# Power_ClockLed.net
KiCad netlist of a schematic drawn in Altium Designer
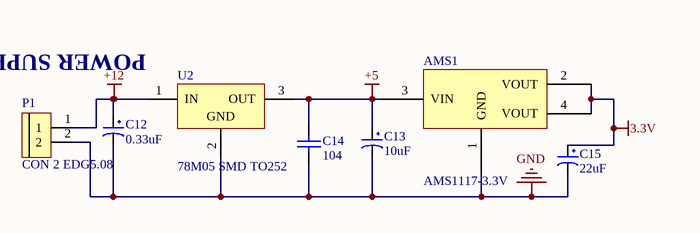
[diagram p0: Power_ClockLed.SchDoc]

(export (version "E")
  (design (tool "Eeschema 10.0.6"))
  (components
    (comp (ref "AMS1")
      (value "AMS1117-3.3V")
      (footprint "SOT223")
      (description "Dán")
      (libsource (lib "Altium_Lib_by_KhueNguyenCreator") (part "AMS1117 SMD"))
    )
    (comp (ref "C12")
      (value "0.33uF")
      (footprint "tu hoa 5mm")
      (description "Cắm")
      (libsource (lib "Altium_Lib_by_KhueNguyenCreator") (part "Tu Hoa 0.33uF 50V 5x11"))
    )
    (comp (ref "C13")
      (value "10uF")
      (footprint "tu hoa 13mm")
      (description "Cắm")
      (libsource (lib "Altium_Lib_by_KhueNguyenCreator") (part "Tu Hoa 10uF 450V 13x20"))
    )
    (comp (ref "C14")
      (value "104")
      (footprint "tu 0805")
      (description "Dán")
      (libsource (lib "Altium_Lib_by_KhueNguyenCreator") (part "Tu 0805 104 50V 10%"))
    )
    (comp (ref "C15")
      (value "22uF")
      (footprint "tu hoa 5mm")
      (description "Cắm")
      (libsource (lib "Altium_Lib_by_KhueNguyenCreator") (part "Tu Hoa 22uF 35V 5x11"))
    )
    (comp (ref "P1")
      (value "CON 2 EDG5.08")
      (footprint "CON 2 2EDG5.08")
      (description "Cắm")
      (libsource (lib "Altium_Lib_by_KhueNguyenCreator") (part "CON 2 EDG5.08"))
    )
    (comp (ref "U2")
      (value "78M05 SMD TO252")
      (footprint "TO252")
      (description "Dán")
      (libsource (lib "Altium_Lib_by_KhueNguyenCreator") (part "78M05 SMD TO252"))
    )
  )
  (nets
    (net (code "1") (name "+5") (class "Default")
      (node (ref "AMS1") (pin "3") (pinfunction "VIN_3") (pintype "passive"))
      (node (ref "C13") (pin "1") (pinfunction "1_1") (pintype "passive"))
      (node (ref "C14") (pin "1") (pinfunction "1_1") (pintype "passive"))
      (node (ref "U2") (pin "3") (pinfunction "OUT_3") (pintype "power_in"))
    )
    (net (code "2") (name "+12") (class "Default")
      (node (ref "C12") (pin "1") (pinfunction "1_1") (pintype "passive"))
      (node (ref "P1") (pin "1") (pinfunction "1_1") (pintype "passive"))
      (node (ref "U2") (pin "1") (pinfunction "IN_1") (pintype "power_in"))
    )
    (net (code "3") (name "3.3V") (class "Default")
      (node (ref "AMS1") (pin "2") (pinfunction "VOUT_2") (pintype "passive"))
      (node (ref "AMS1") (pin "4") (pinfunction "VOUT_4") (pintype "passive"))
      (node (ref "C15") (pin "1") (pinfunction "1_1") (pintype "passive"))
    )
    (net (code "4") (name "GND") (class "Default")
      (node (ref "AMS1") (pin "1") (pinfunction "GND_1") (pintype "passive"))
      (node (ref "C12") (pin "2") (pinfunction "2_2") (pintype "passive"))
      (node (ref "C13") (pin "2") (pinfunction "2_2") (pintype "passive"))
      (node (ref "C14") (pin "2") (pinfunction "2_2") (pintype "passive"))
      (node (ref "C15") (pin "2") (pinfunction "2_2") (pintype "passive"))
      (node (ref "P1") (pin "2") (pinfunction "2_2") (pintype "passive"))
      (node (ref "U2") (pin "2") (pinfunction "GND_2") (pintype "power_in"))
    )
  )
)
